# I2CRJ45X8.net
KiCad netlist of a schematic drawn in EAGLE
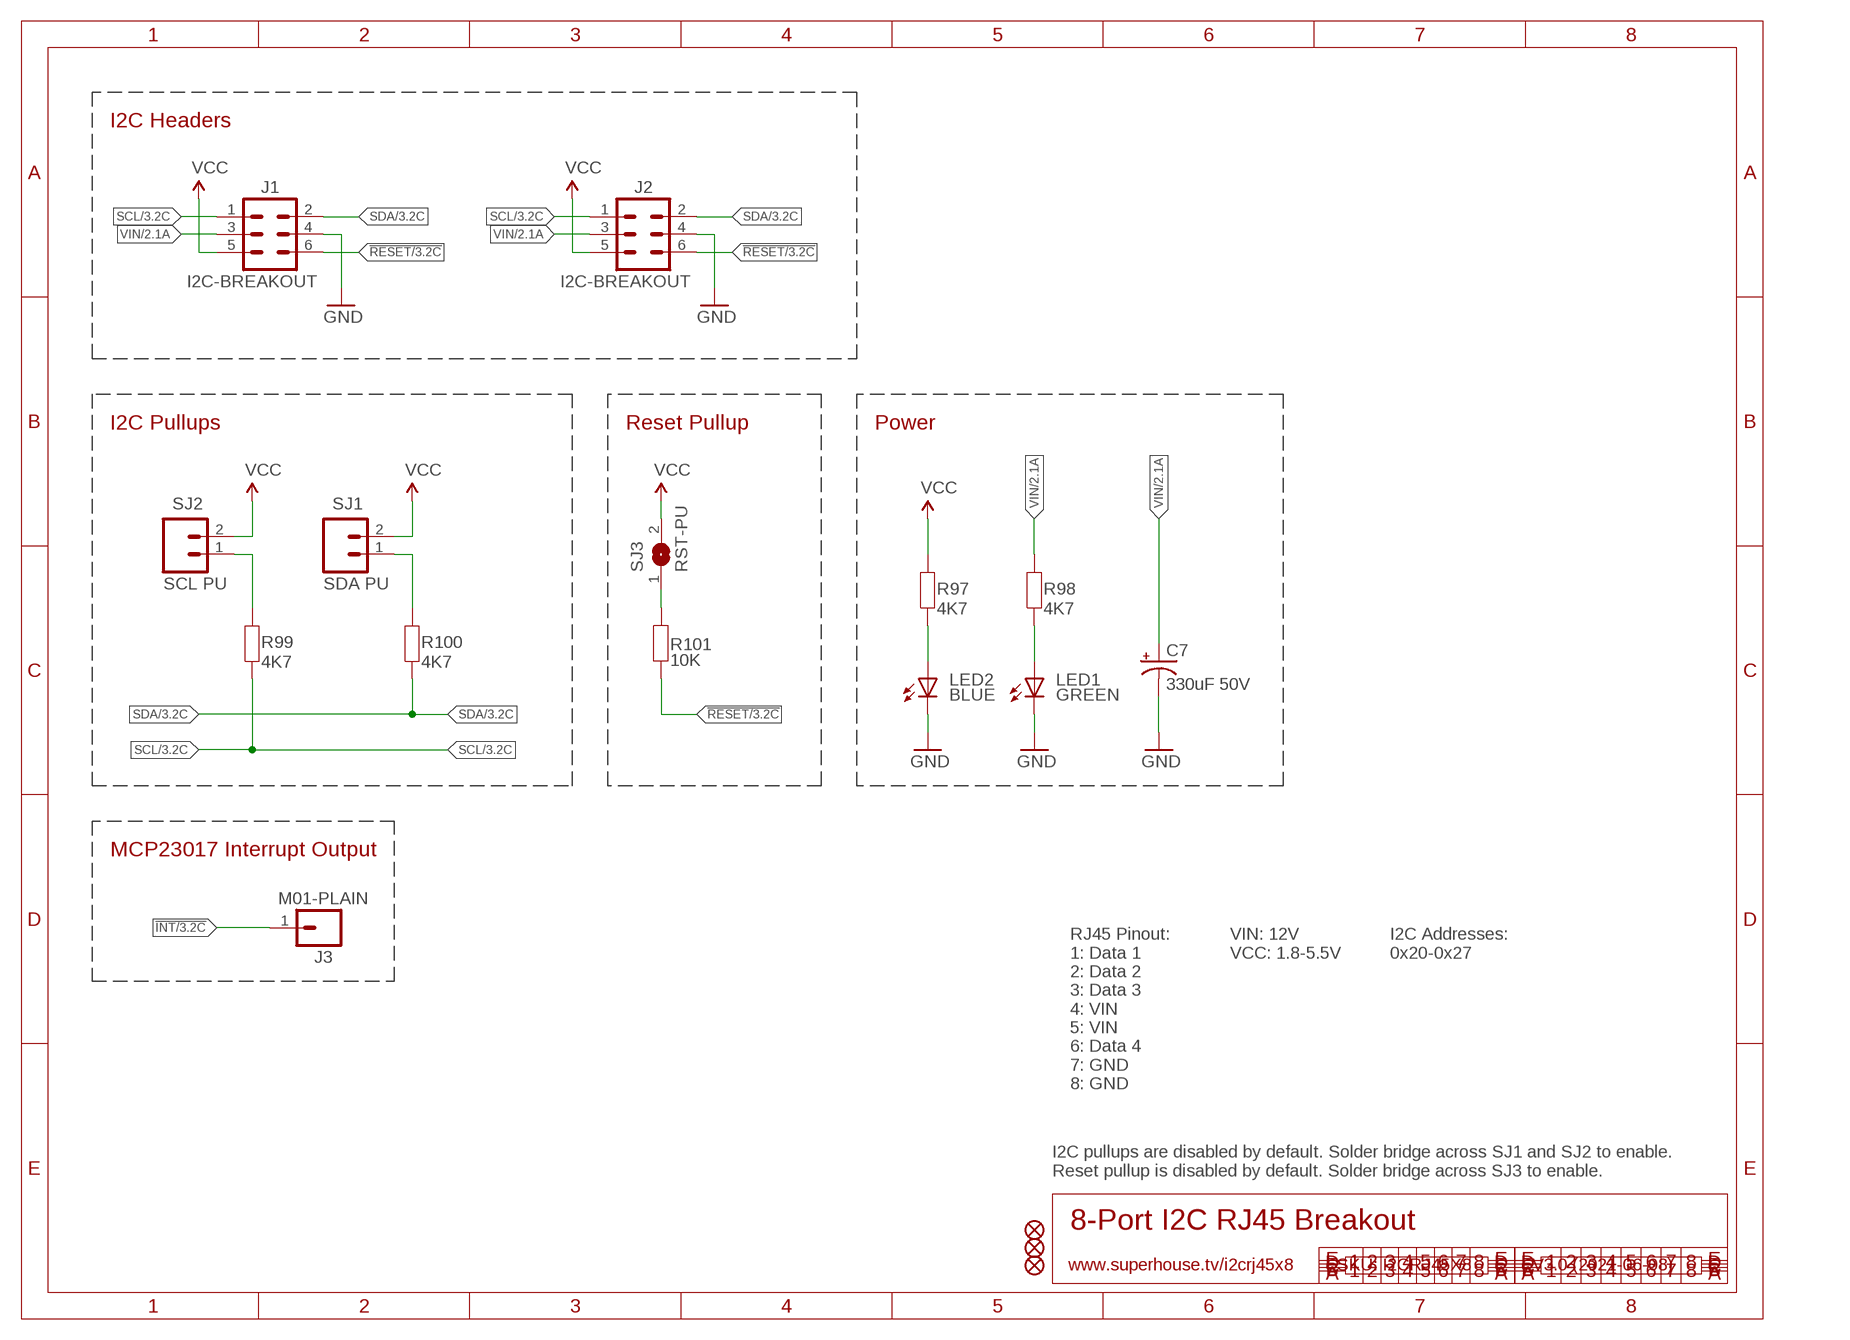
[diagram p0: schematic, sheet 1]
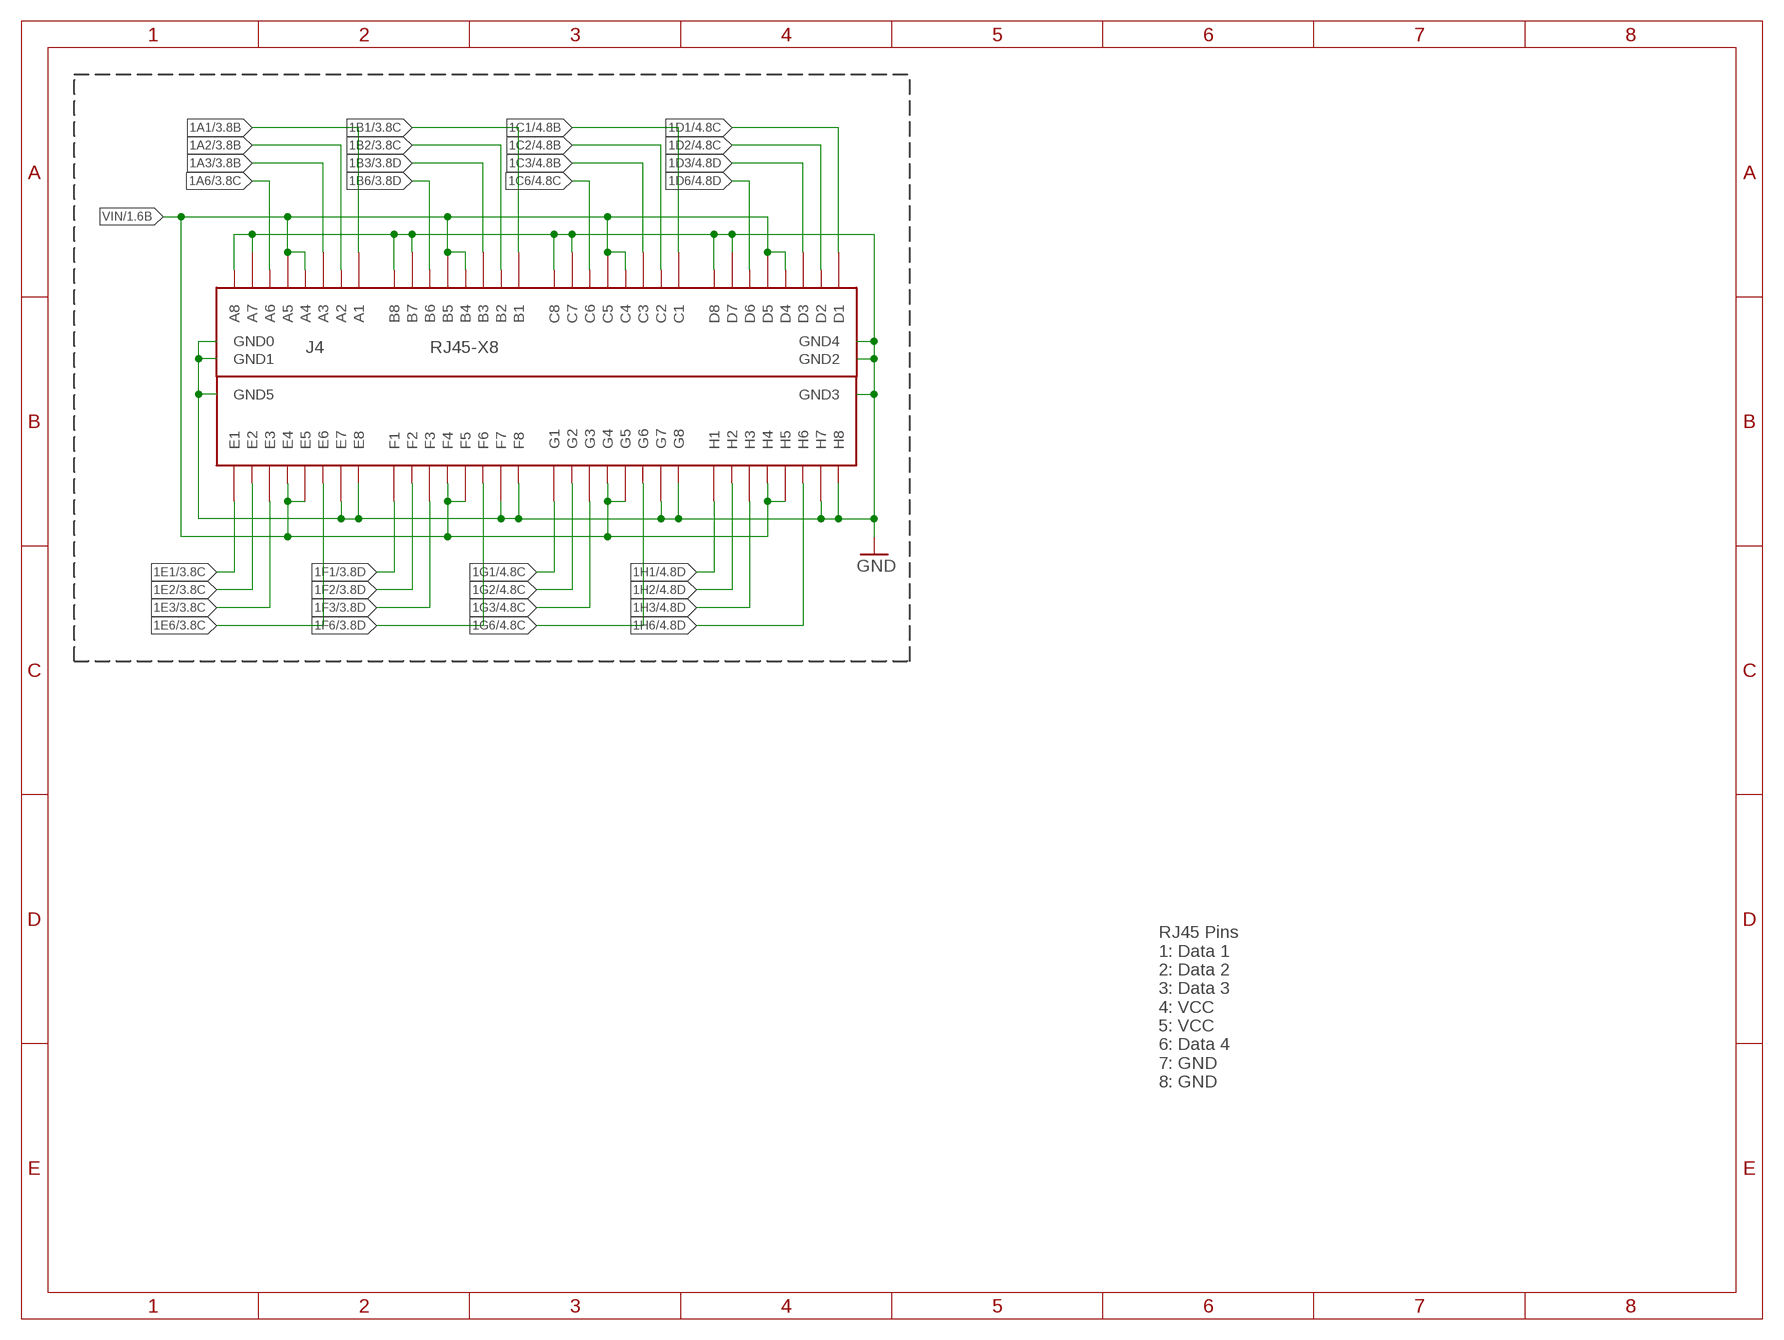
[diagram p1: schematic, sheet 2]
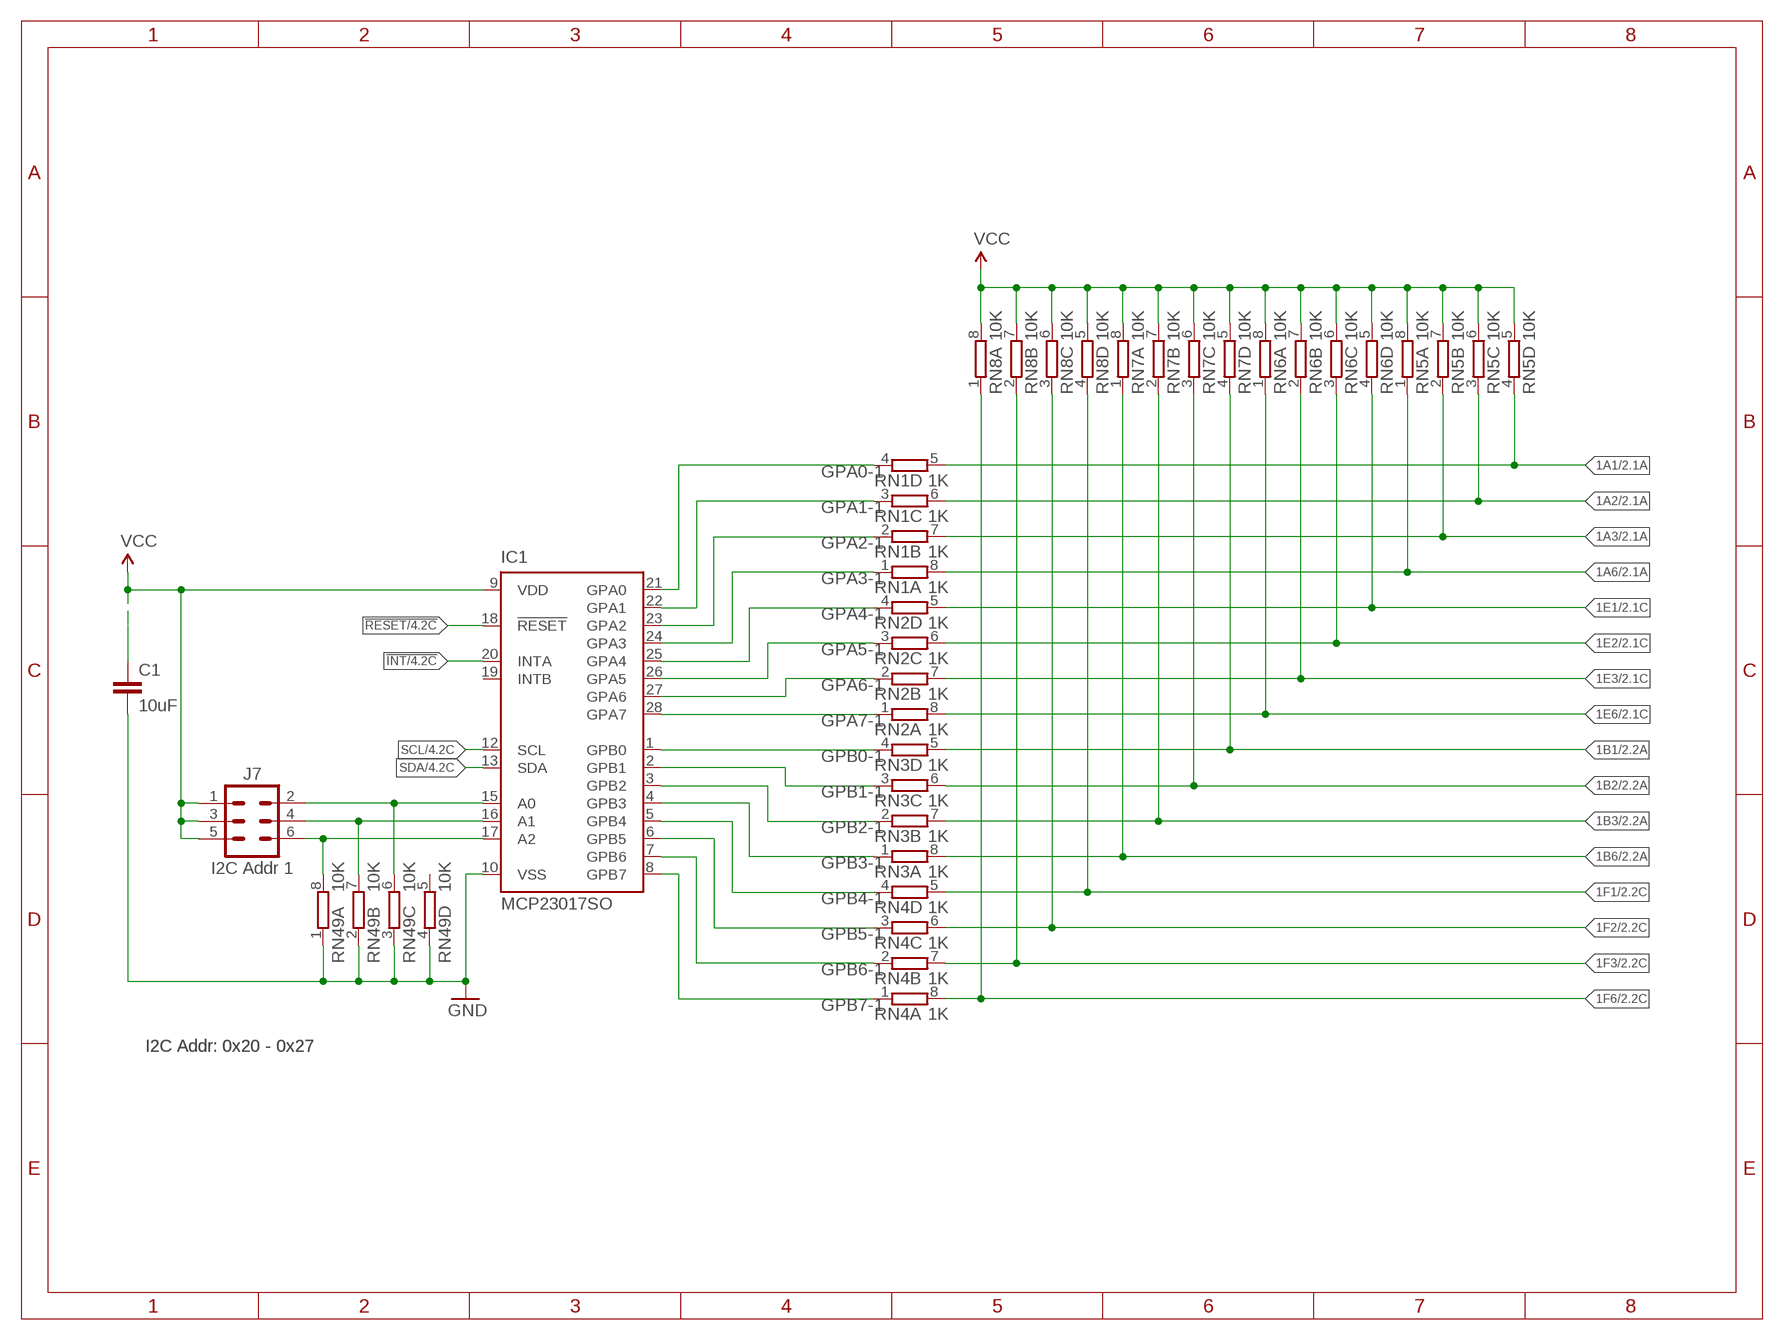
[diagram p2: schematic, sheet 3]
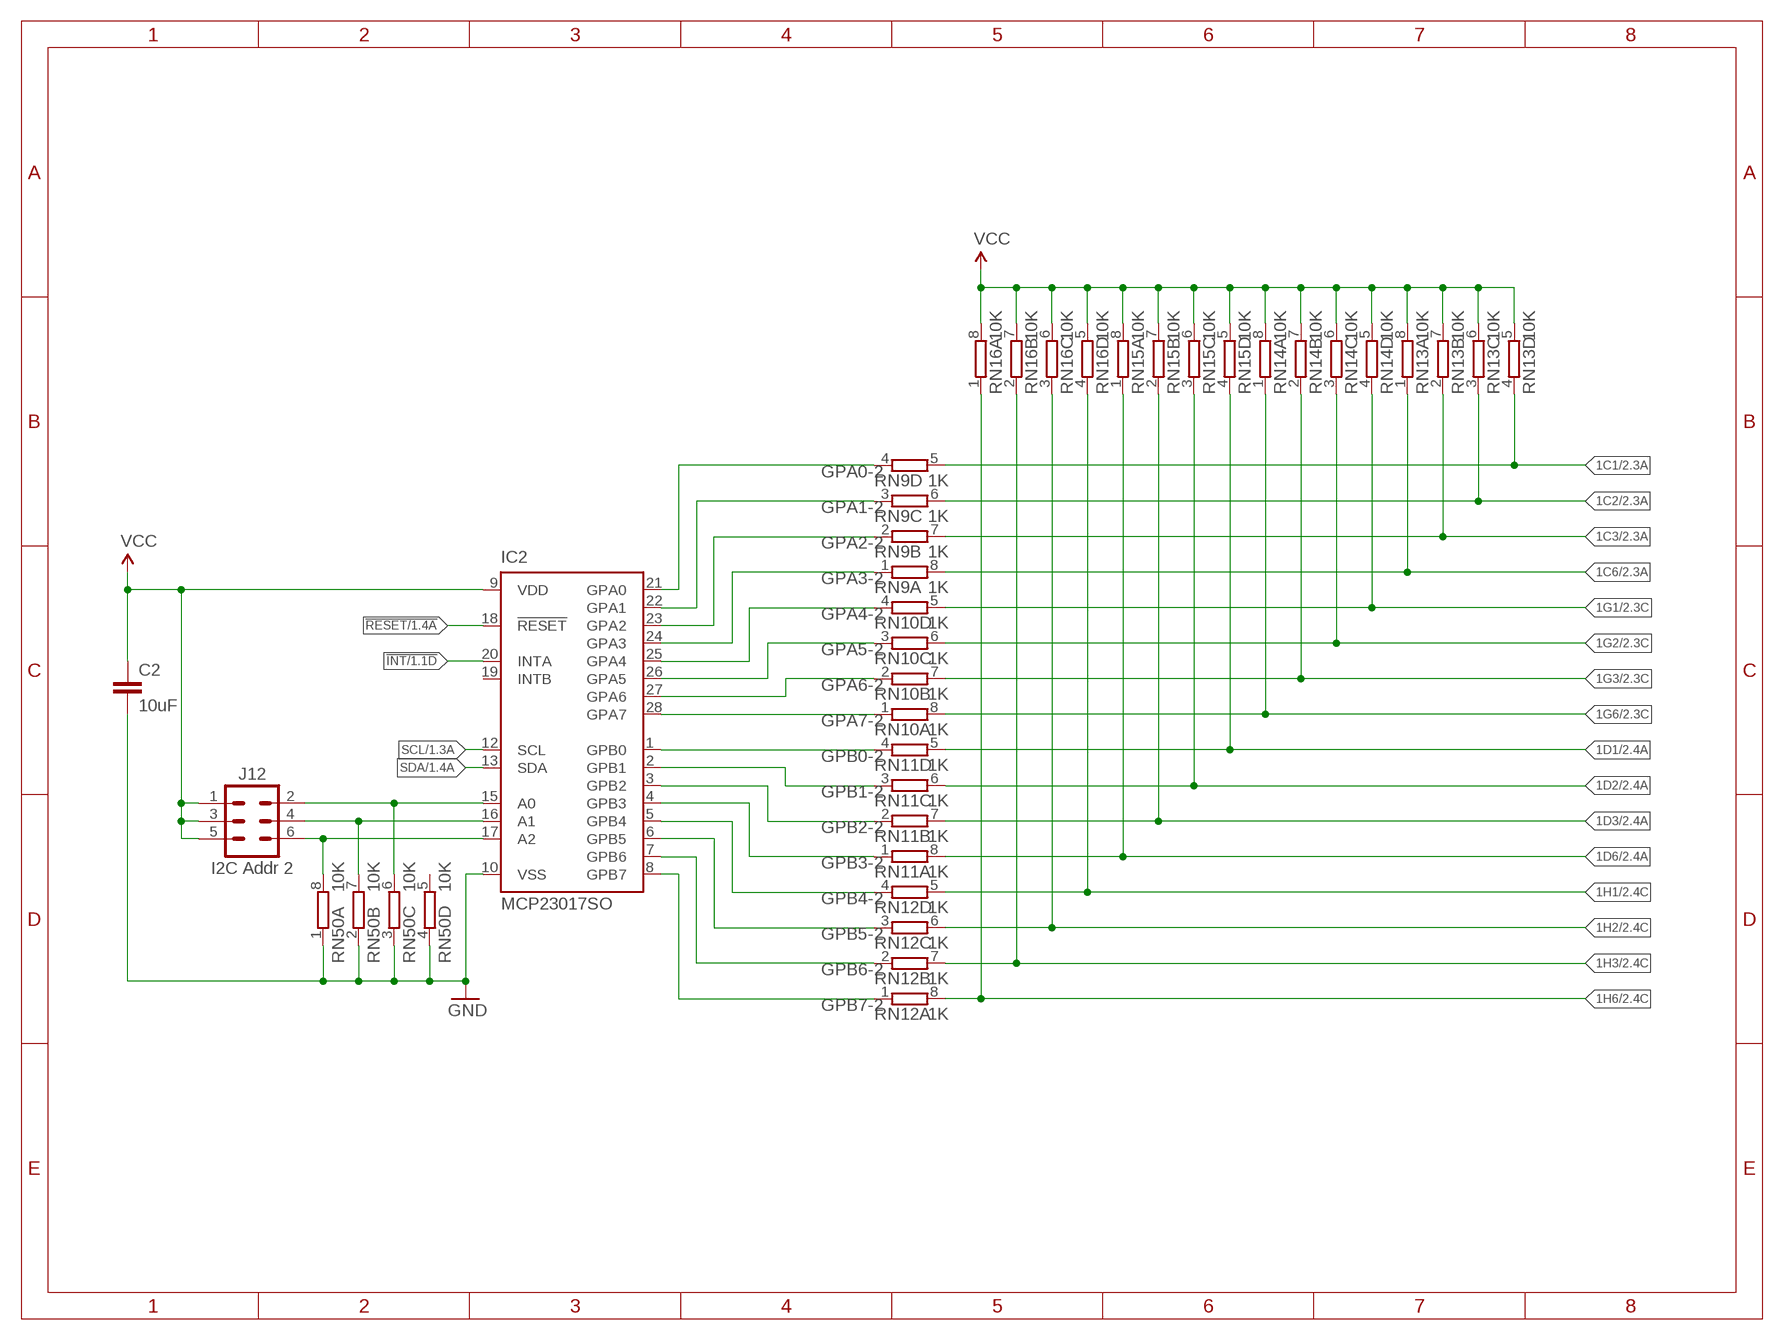
[diagram p3: schematic, sheet 4]

(export (version "E")
  (design (tool "Eeschema 10.0.6"))
  (components
    (comp (ref "C2")
      (value "10uF")
      (footprint "eagle-import:C0805")
      (libsource (lib "eagle-import") (part "CAP0805"))
    )
    (comp (ref "IC2")
      (value "MCP23017SO")
      (footprint "eagle-import:SO28W")
      (libsource (lib "eagle-import") (part "MCP23017SO"))
    )
    (comp (ref "J12")
      (value "I2C Addr 2")
      (footprint "eagle-import:2X03-P")
      (libsource (lib "eagle-import") (part "M02X3-PIN"))
    )
    (comp (ref "RN9")
      (value "1K")
      (footprint "eagle-import:CAY16")
      (libsource (lib "eagle-import") (part "4R-NCAY16"))
    )
    (comp (ref "RN10")
      (value "1K")
      (footprint "eagle-import:CAY16")
      (libsource (lib "eagle-import") (part "4R-NCAY16"))
    )
    (comp (ref "RN11")
      (value "1K")
      (footprint "eagle-import:CAY16")
      (libsource (lib "eagle-import") (part "4R-NCAY16"))
    )
    (comp (ref "RN12")
      (value "1K")
      (footprint "eagle-import:CAY16")
      (libsource (lib "eagle-import") (part "4R-NCAY16"))
    )
    (comp (ref "RN13")
      (value "10K")
      (footprint "eagle-import:CAY16")
      (libsource (lib "eagle-import") (part "4R-NCAY16"))
    )
    (comp (ref "RN14")
      (value "10K")
      (footprint "eagle-import:CAY16")
      (libsource (lib "eagle-import") (part "4R-NCAY16"))
    )
    (comp (ref "RN15")
      (value "10K")
      (footprint "eagle-import:CAY16")
      (libsource (lib "eagle-import") (part "4R-NCAY16"))
    )
    (comp (ref "RN16")
      (value "10K")
      (footprint "eagle-import:CAY16")
      (libsource (lib "eagle-import") (part "4R-NCAY16"))
    )
    (comp (ref "RN50")
      (value "10K")
      (footprint "eagle-import:CAY16")
      (libsource (lib "eagle-import") (part "4R-NCAY16"))
    )
    (comp (ref "J4")
      (value "RJ45-X8")
      (footprint "eagle-import:RJ45-2X4")
      (libsource (lib "eagle-import") (part "RJ45-X8"))
    )
    (comp (ref "C7")
      (value "330uF 50V")
      (footprint "eagle-import:PANASONIC_G")
      (libsource (lib "eagle-import") (part "CAP_POLG"))
    )
    (comp (ref "FID1")
      (value "FIDUCIAL1X2.5")
      (footprint "eagle-import:FIDUCIAL-1X2.5")
      (libsource (lib "eagle-import") (part "FIDUCIAL1X2.5"))
    )
    (comp (ref "FID2")
      (value "FIDUCIAL1X2.5")
      (footprint "eagle-import:FIDUCIAL-1X2.5")
      (libsource (lib "eagle-import") (part "FIDUCIAL1X2.5"))
    )
    (comp (ref "FID3")
      (value "FIDUCIAL1X2.5")
      (footprint "eagle-import:FIDUCIAL-1X2.5")
      (libsource (lib "eagle-import") (part "FIDUCIAL1X2.5"))
    )
    (comp (ref "J1")
      (value "I2C-BREAKOUT")
      (footprint "eagle-import:2X3-2.54-SHROUDED")
      (libsource (lib "eagle-import") (part "M02X3-SHROUDED"))
    )
    (comp (ref "J2")
      (value "I2C-BREAKOUT")
      (footprint "eagle-import:2X3-2.54-SHROUDED")
      (libsource (lib "eagle-import") (part "M02X3-SHROUDED"))
    )
    (comp (ref "J3")
      (value "M01-PLAIN")
      (footprint "eagle-import:1X01")
      (libsource (lib "eagle-import") (part "M01-PLAIN"))
    )
    (comp (ref "LED1")
      (value "GREEN")
      (footprint "eagle-import:LED-0603")
      (libsource (lib "eagle-import") (part "LED0603"))
    )
    (comp (ref "LED2")
      (value "BLUE")
      (footprint "eagle-import:LED-0603")
      (libsource (lib "eagle-import") (part "LED0603"))
    )
    (comp (ref "R97")
      (value "4K7")
      (footprint "eagle-import:R0603")
      (libsource (lib "eagle-import") (part "RESISTOR0603"))
    )
    (comp (ref "R98")
      (value "4K7")
      (footprint "eagle-import:R0603")
      (libsource (lib "eagle-import") (part "RESISTOR0603"))
    )
    (comp (ref "R99")
      (value "4K7")
      (footprint "eagle-import:R0603")
      (libsource (lib "eagle-import") (part "RESISTOR0603"))
    )
    (comp (ref "R100")
      (value "4K7")
      (footprint "eagle-import:R0603")
      (libsource (lib "eagle-import") (part "RESISTOR0603"))
    )
    (comp (ref "R101")
      (value "10K")
      (footprint "eagle-import:R0603")
      (libsource (lib "eagle-import") (part "RESISTOR0603"))
    )
    (comp (ref "SJ1")
      (value "SDA PU")
      (footprint "eagle-import:1X02-P")
      (libsource (lib "eagle-import") (part "M02-PIN"))
    )
    (comp (ref "SJ2")
      (value "SCL PU")
      (footprint "eagle-import:1X02-P")
      (libsource (lib "eagle-import") (part "M02-PIN"))
    )
    (comp (ref "SJ3")
      (value "RST-PU")
      (footprint "eagle-import:SJ")
      (libsource (lib "eagle-import") (part "SJ-NORMAL"))
    )
    (comp (ref "C1")
      (value "10uF")
      (footprint "eagle-import:C0805")
      (libsource (lib "eagle-import") (part "CAP0805"))
    )
    (comp (ref "IC1")
      (value "MCP23017SO")
      (footprint "eagle-import:SO28W")
      (libsource (lib "eagle-import") (part "MCP23017SO"))
    )
    (comp (ref "J7")
      (value "I2C Addr 1")
      (footprint "eagle-import:2X03-P")
      (libsource (lib "eagle-import") (part "M02X3-PIN"))
    )
    (comp (ref "RN1")
      (value "1K")
      (footprint "eagle-import:CAY16")
      (libsource (lib "eagle-import") (part "4R-NCAY16"))
    )
    (comp (ref "RN2")
      (value "1K")
      (footprint "eagle-import:CAY16")
      (libsource (lib "eagle-import") (part "4R-NCAY16"))
    )
    (comp (ref "RN3")
      (value "1K")
      (footprint "eagle-import:CAY16")
      (libsource (lib "eagle-import") (part "4R-NCAY16"))
    )
    (comp (ref "RN4")
      (value "1K")
      (footprint "eagle-import:CAY16")
      (libsource (lib "eagle-import") (part "4R-NCAY16"))
    )
    (comp (ref "RN5")
      (value "10K")
      (footprint "eagle-import:CAY16")
      (libsource (lib "eagle-import") (part "4R-NCAY16"))
    )
    (comp (ref "RN6")
      (value "10K")
      (footprint "eagle-import:CAY16")
      (libsource (lib "eagle-import") (part "4R-NCAY16"))
    )
    (comp (ref "RN7")
      (value "10K")
      (footprint "eagle-import:CAY16")
      (libsource (lib "eagle-import") (part "4R-NCAY16"))
    )
    (comp (ref "RN8")
      (value "10K")
      (footprint "eagle-import:CAY16")
      (libsource (lib "eagle-import") (part "4R-NCAY16"))
    )
    (comp (ref "RN49")
      (value "10K")
      (footprint "eagle-import:CAY16")
      (libsource (lib "eagle-import") (part "4R-NCAY16"))
    )
  )
  (nets
    (net (code "1") (name "1A1") (class "Default")
      (node (ref "J4") (pin "A1") (pinfunction "A1_A1") (pintype "bidirectional"))
      (node (ref "RN1") (pin "5") (pinfunction "2_5") (pintype "passive"))
      (node (ref "RN5") (pin "4") (pinfunction "1_4") (pintype "passive"))
    )
    (net (code "2") (name "1A2") (class "Default")
      (node (ref "J4") (pin "A2") (pinfunction "A2_A2") (pintype "bidirectional"))
      (node (ref "RN1") (pin "6") (pinfunction "2_6") (pintype "passive"))
      (node (ref "RN5") (pin "3") (pinfunction "1_3") (pintype "passive"))
    )
    (net (code "3") (name "1A3") (class "Default")
      (node (ref "J4") (pin "A3") (pinfunction "A3_A3") (pintype "bidirectional"))
      (node (ref "RN1") (pin "7") (pinfunction "2_7") (pintype "passive"))
      (node (ref "RN5") (pin "2") (pinfunction "1_2") (pintype "passive"))
    )
    (net (code "4") (name "1A6") (class "Default")
      (node (ref "J4") (pin "A6") (pinfunction "A6_A6") (pintype "bidirectional"))
      (node (ref "RN1") (pin "8") (pinfunction "2_8") (pintype "passive"))
      (node (ref "RN5") (pin "1") (pinfunction "1_1") (pintype "passive"))
    )
    (net (code "5") (name "1B1") (class "Default")
      (node (ref "J4") (pin "B1") (pinfunction "B1_B1") (pintype "bidirectional"))
      (node (ref "RN3") (pin "5") (pinfunction "2_5") (pintype "passive"))
      (node (ref "RN7") (pin "4") (pinfunction "1_4") (pintype "passive"))
    )
    (net (code "6") (name "1B2") (class "Default")
      (node (ref "J4") (pin "B2") (pinfunction "B2_B2") (pintype "bidirectional"))
      (node (ref "RN3") (pin "6") (pinfunction "2_6") (pintype "passive"))
      (node (ref "RN7") (pin "3") (pinfunction "1_3") (pintype "passive"))
    )
    (net (code "7") (name "1B3") (class "Default")
      (node (ref "J4") (pin "B3") (pinfunction "B3_B3") (pintype "bidirectional"))
      (node (ref "RN3") (pin "7") (pinfunction "2_7") (pintype "passive"))
      (node (ref "RN7") (pin "2") (pinfunction "1_2") (pintype "passive"))
    )
    (net (code "8") (name "1B6") (class "Default")
      (node (ref "J4") (pin "B6") (pinfunction "B6_B6") (pintype "bidirectional"))
      (node (ref "RN3") (pin "8") (pinfunction "2_8") (pintype "passive"))
      (node (ref "RN7") (pin "1") (pinfunction "1_1") (pintype "passive"))
    )
    (net (code "9") (name "1C1") (class "Default")
      (node (ref "J4") (pin "C1") (pinfunction "C1_C1") (pintype "bidirectional"))
      (node (ref "RN13") (pin "4") (pinfunction "1_4") (pintype "passive"))
      (node (ref "RN9") (pin "5") (pinfunction "2_5") (pintype "passive"))
    )
    (net (code "10") (name "1C2") (class "Default")
      (node (ref "J4") (pin "C2") (pinfunction "C2_C2") (pintype "bidirectional"))
      (node (ref "RN13") (pin "3") (pinfunction "1_3") (pintype "passive"))
      (node (ref "RN9") (pin "6") (pinfunction "2_6") (pintype "passive"))
    )
    (net (code "11") (name "1C3") (class "Default")
      (node (ref "J4") (pin "C3") (pinfunction "C3_C3") (pintype "bidirectional"))
      (node (ref "RN13") (pin "2") (pinfunction "1_2") (pintype "passive"))
      (node (ref "RN9") (pin "7") (pinfunction "2_7") (pintype "passive"))
    )
    (net (code "12") (name "1C6") (class "Default")
      (node (ref "J4") (pin "C6") (pinfunction "C6_C6") (pintype "bidirectional"))
      (node (ref "RN13") (pin "1") (pinfunction "1_1") (pintype "passive"))
      (node (ref "RN9") (pin "8") (pinfunction "2_8") (pintype "passive"))
    )
    (net (code "13") (name "1D1") (class "Default")
      (node (ref "J4") (pin "D1") (pinfunction "D1_D1") (pintype "bidirectional"))
      (node (ref "RN11") (pin "5") (pinfunction "2_5") (pintype "passive"))
      (node (ref "RN15") (pin "4") (pinfunction "1_4") (pintype "passive"))
    )
    (net (code "14") (name "1D2") (class "Default")
      (node (ref "J4") (pin "D2") (pinfunction "D2_D2") (pintype "bidirectional"))
      (node (ref "RN11") (pin "6") (pinfunction "2_6") (pintype "passive"))
      (node (ref "RN15") (pin "3") (pinfunction "1_3") (pintype "passive"))
    )
    (net (code "15") (name "1D3") (class "Default")
      (node (ref "J4") (pin "D3") (pinfunction "D3_D3") (pintype "bidirectional"))
      (node (ref "RN11") (pin "7") (pinfunction "2_7") (pintype "passive"))
      (node (ref "RN15") (pin "2") (pinfunction "1_2") (pintype "passive"))
    )
    (net (code "16") (name "1D6") (class "Default")
      (node (ref "J4") (pin "D6") (pinfunction "D6_D6") (pintype "bidirectional"))
      (node (ref "RN11") (pin "8") (pinfunction "2_8") (pintype "passive"))
      (node (ref "RN15") (pin "1") (pinfunction "1_1") (pintype "passive"))
    )
    (net (code "17") (name "1E1") (class "Default")
      (node (ref "J4") (pin "E1") (pinfunction "E1_E1") (pintype "bidirectional"))
      (node (ref "RN2") (pin "5") (pinfunction "2_5") (pintype "passive"))
      (node (ref "RN6") (pin "4") (pinfunction "1_4") (pintype "passive"))
    )
    (net (code "18") (name "1E2") (class "Default")
      (node (ref "J4") (pin "E2") (pinfunction "E2_E2") (pintype "bidirectional"))
      (node (ref "RN2") (pin "6") (pinfunction "2_6") (pintype "passive"))
      (node (ref "RN6") (pin "3") (pinfunction "1_3") (pintype "passive"))
    )
    (net (code "19") (name "1E3") (class "Default")
      (node (ref "J4") (pin "E3") (pinfunction "E3_E3") (pintype "bidirectional"))
      (node (ref "RN2") (pin "7") (pinfunction "2_7") (pintype "passive"))
      (node (ref "RN6") (pin "2") (pinfunction "1_2") (pintype "passive"))
    )
    (net (code "20") (name "1E6") (class "Default")
      (node (ref "J4") (pin "E6") (pinfunction "E6_E6") (pintype "bidirectional"))
      (node (ref "RN2") (pin "8") (pinfunction "2_8") (pintype "passive"))
      (node (ref "RN6") (pin "1") (pinfunction "1_1") (pintype "passive"))
    )
    (net (code "21") (name "1F1") (class "Default")
      (node (ref "J4") (pin "F1") (pinfunction "F1_F1") (pintype "bidirectional"))
      (node (ref "RN4") (pin "5") (pinfunction "2_5") (pintype "passive"))
      (node (ref "RN8") (pin "4") (pinfunction "1_4") (pintype "passive"))
    )
    (net (code "22") (name "1F2") (class "Default")
      (node (ref "J4") (pin "F2") (pinfunction "F2_F2") (pintype "bidirectional"))
      (node (ref "RN4") (pin "6") (pinfunction "2_6") (pintype "passive"))
      (node (ref "RN8") (pin "3") (pinfunction "1_3") (pintype "passive"))
    )
    (net (code "23") (name "1F3") (class "Default")
      (node (ref "J4") (pin "F3") (pinfunction "F3_F3") (pintype "bidirectional"))
      (node (ref "RN4") (pin "7") (pinfunction "2_7") (pintype "passive"))
      (node (ref "RN8") (pin "2") (pinfunction "1_2") (pintype "passive"))
    )
    (net (code "24") (name "1F6") (class "Default")
      (node (ref "J4") (pin "F6") (pinfunction "F6_F6") (pintype "bidirectional"))
      (node (ref "RN4") (pin "8") (pinfunction "2_8") (pintype "passive"))
      (node (ref "RN8") (pin "1") (pinfunction "1_1") (pintype "passive"))
    )
    (net (code "25") (name "1G1") (class "Default")
      (node (ref "J4") (pin "G1") (pinfunction "G1_G1") (pintype "bidirectional"))
      (node (ref "RN10") (pin "5") (pinfunction "2_5") (pintype "passive"))
      (node (ref "RN14") (pin "4") (pinfunction "1_4") (pintype "passive"))
    )
    (net (code "26") (name "1G2") (class "Default")
      (node (ref "J4") (pin "G2") (pinfunction "G2_G2") (pintype "bidirectional"))
      (node (ref "RN10") (pin "6") (pinfunction "2_6") (pintype "passive"))
      (node (ref "RN14") (pin "3") (pinfunction "1_3") (pintype "passive"))
    )
    (net (code "27") (name "1G3") (class "Default")
      (node (ref "J4") (pin "G3") (pinfunction "G3_G3") (pintype "bidirectional"))
      (node (ref "RN10") (pin "7") (pinfunction "2_7") (pintype "passive"))
      (node (ref "RN14") (pin "2") (pinfunction "1_2") (pintype "passive"))
    )
    (net (code "28") (name "1G6") (class "Default")
      (node (ref "J4") (pin "G6") (pinfunction "G6_G6") (pintype "bidirectional"))
      (node (ref "RN10") (pin "8") (pinfunction "2_8") (pintype "passive"))
      (node (ref "RN14") (pin "1") (pinfunction "1_1") (pintype "passive"))
    )
    (net (code "29") (name "1H1") (class "Default")
      (node (ref "J4") (pin "H1") (pinfunction "H1_H1") (pintype "bidirectional"))
      (node (ref "RN12") (pin "5") (pinfunction "2_5") (pintype "passive"))
      (node (ref "RN16") (pin "4") (pinfunction "1_4") (pintype "passive"))
    )
    (net (code "30") (name "1H2") (class "Default")
      (node (ref "J4") (pin "H2") (pinfunction "H2_H2") (pintype "bidirectional"))
      (node (ref "RN12") (pin "6") (pinfunction "2_6") (pintype "passive"))
      (node (ref "RN16") (pin "3") (pinfunction "1_3") (pintype "passive"))
    )
    (net (code "31") (name "1H3") (class "Default")
      (node (ref "J4") (pin "H3") (pinfunction "H3_H3") (pintype "bidirectional"))
      (node (ref "RN12") (pin "7") (pinfunction "2_7") (pintype "passive"))
      (node (ref "RN16") (pin "2") (pinfunction "1_2") (pintype "passive"))
    )
    (net (code "32") (name "1H6") (class "Default")
      (node (ref "J4") (pin "H6") (pinfunction "H6_H6") (pintype "bidirectional"))
      (node (ref "RN12") (pin "8") (pinfunction "2_8") (pintype "passive"))
      (node (ref "RN16") (pin "1") (pinfunction "1_1") (pintype "passive"))
    )
    (net (code "33") (name "GND") (class "Default")
      (node (ref "C1") (pin "2") (pinfunction "2_2") (pintype "passive"))
      (node (ref "C2") (pin "2") (pinfunction "2_2") (pintype "passive"))
      (node (ref "C7") (pin "-") (pinfunction "-_-") (pintype "passive"))
      (node (ref "IC1") (pin "10") (pinfunction "VSS_10") (pintype "power_in"))
      (node (ref "IC2") (pin "10") (pinfunction "VSS_10") (pintype "power_in"))
      (node (ref "J1") (pin "4") (pinfunction "4_4") (pintype "passive"))
      (node (ref "J2") (pin "4") (pinfunction "4_4") (pintype "passive"))
      (node (ref "J4") (pin "A7") (pinfunction "A7_A7") (pintype "bidirectional"))
      (node (ref "J4") (pin "A8") (pinfunction "A8_A8") (pintype "bidirectional"))
      (node (ref "J4") (pin "B7") (pinfunction "B7_B7") (pintype "bidirectional"))
      (node (ref "J4") (pin "B8") (pinfunction "B8_B8") (pintype "bidirectional"))
      (node (ref "J4") (pin "C7") (pinfunction "C7_C7") (pintype "bidirectional"))
      (node (ref "J4") (pin "C8") (pinfunction "C8_C8") (pintype "bidirectional"))
      (node (ref "J4") (pin "D7") (pinfunction "D7_D7") (pintype "bidirectional"))
      (node (ref "J4") (pin "D8") (pinfunction "D8_D8") (pintype "bidirectional"))
      (node (ref "J4") (pin "E7") (pinfunction "E7_E7") (pintype "bidirectional"))
      (node (ref "J4") (pin "E8") (pinfunction "E8_E8") (pintype "bidirectional"))
      (node (ref "J4") (pin "F7") (pinfunction "F7_F7") (pintype "bidirectional"))
      (node (ref "J4") (pin "F8") (pinfunction "F8_F8") (pintype "bidirectional"))
      (node (ref "J4") (pin "G7") (pinfunction "G7_G7") (pintype "bidirectional"))
      (node (ref "J4") (pin "G8") (pinfunction "G8_G8") (pintype "bidirectional"))
      (node (ref "J4") (pin "GND0") (pinfunction "GND0_GND0") (pintype "power_in"))
      (node (ref "J4") (pin "GND1") (pinfunction "GND1_GND1") (pintype "power_in"))
      (node (ref "J4") (pin "GND2") (pinfunction "GND2_GND2") (pintype "power_in"))
      (node (ref "J4") (pin "GND3") (pinfunction "GND3_GND3") (pintype "power_in"))
      (node (ref "J4") (pin "GND4") (pinfunction "GND4_GND4") (pintype "power_in"))
      (node (ref "J4") (pin "GND5") (pinfunction "GND5_GND5") (pintype "power_in"))
      (node (ref "J4") (pin "H7") (pinfunction "H7_H7") (pintype "bidirectional"))
      (node (ref "J4") (pin "H8") (pinfunction "H8_H8") (pintype "bidirectional"))
      (node (ref "LED1") (pin "C") (pinfunction "C_C") (pintype "passive"))
      (node (ref "LED2") (pin "C") (pinfunction "C_C") (pintype "passive"))
      (node (ref "RN49") (pin "1") (pinfunction "1_1") (pintype "passive"))
      (node (ref "RN49") (pin "2") (pinfunction "1_2") (pintype "passive"))
      (node (ref "RN49") (pin "3") (pinfunction "1_3") (pintype "passive"))
      (node (ref "RN49") (pin "4") (pinfunction "1_4") (pintype "passive"))
      (node (ref "RN50") (pin "1") (pinfunction "1_1") (pintype "passive"))
      (node (ref "RN50") (pin "2") (pinfunction "1_2") (pintype "passive"))
      (node (ref "RN50") (pin "3") (pinfunction "1_3") (pintype "passive"))
      (node (ref "RN50") (pin "4") (pinfunction "1_4") (pintype "passive"))
    )
    (net (code "34") (name "GPA0-1") (class "Default")
      (node (ref "IC1") (pin "21") (pinfunction "GPA0_21") (pintype "bidirectional"))
      (node (ref "RN1") (pin "4") (pinfunction "1_4") (pintype "passive"))
    )
    (net (code "35") (name "GPA0-2") (class "Default")
      (node (ref "IC2") (pin "21") (pinfunction "GPA0_21") (pintype "bidirectional"))
      (node (ref "RN9") (pin "4") (pinfunction "1_4") (pintype "passive"))
    )
    (net (code "36") (name "GPA1-1") (class "Default")
      (node (ref "IC1") (pin "22") (pinfunction "GPA1_22") (pintype "bidirectional"))
      (node (ref "RN1") (pin "3") (pinfunction "1_3") (pintype "passive"))
    )
    (net (code "37") (name "GPA1-2") (class "Default")
      (node (ref "IC2") (pin "22") (pinfunction "GPA1_22") (pintype "bidirectional"))
      (node (ref "RN9") (pin "3") (pinfunction "1_3") (pintype "passive"))
    )
    (net (code "38") (name "GPA2-1") (class "Default")
      (node (ref "IC1") (pin "23") (pinfunction "GPA2_23") (pintype "bidirectional"))
      (node (ref "RN1") (pin "2") (pinfunction "1_2") (pintype "passive"))
    )
    (net (code "39") (name "GPA2-2") (class "Default")
      (node (ref "IC2") (pin "23") (pinfunction "GPA2_23") (pintype "bidirectional"))
      (node (ref "RN9") (pin "2") (pinfunction "1_2") (pintype "passive"))
    )
    (net (code "40") (name "GPA3-1") (class "Default")
      (node (ref "IC1") (pin "24") (pinfunction "GPA3_24") (pintype "bidirectional"))
      (node (ref "RN1") (pin "1") (pinfunction "1_1") (pintype "passive"))
    )
    (net (code "41") (name "GPA3-2") (class "Default")
      (node (ref "IC2") (pin "24") (pinfunction "GPA3_24") (pintype "bidirectional"))
      (node (ref "RN9") (pin "1") (pinfunction "1_1") (pintype "passive"))
    )
    (net (code "42") (name "GPA4-1") (class "Default")
      (node (ref "IC1") (pin "25") (pinfunction "GPA4_25") (pintype "bidirectional"))
      (node (ref "RN2") (pin "4") (pinfunction "1_4") (pintype "passive"))
    )
    (net (code "43") (name "GPA4-2") (class "Default")
      (node (ref "IC2") (pin "25") (pinfunction "GPA4_25") (pintype "bidirectional"))
      (node (ref "RN10") (pin "4") (pinfunction "1_4") (pintype "passive"))
    )
    (net (code "44") (name "GPA5-1") (class "Default")
      (node (ref "IC1") (pin "26") (pinfunction "GPA5_26") (pintype "bidirectional"))
      (node (ref "RN2") (pin "3") (pinfunction "1_3") (pintype "passive"))
    )
    (net (code "45") (name "GPA5-2") (class "Default")
      (node (ref "IC2") (pin "26") (pinfunction "GPA5_26") (pintype "bidirectional"))
      (node (ref "RN10") (pin "3") (pinfunction "1_3") (pintype "passive"))
    )
    (net (code "46") (name "GPA6-1") (class "Default")
      (node (ref "IC1") (pin "27") (pinfunction "GPA6_27") (pintype "bidirectional"))
      (node (ref "RN2") (pin "2") (pinfunction "1_2") (pintype "passive"))
    )
    (net (code "47") (name "GPA6-2") (class "Default")
      (node (ref "IC2") (pin "27") (pinfunction "GPA6_27") (pintype "bidirectional"))
      (node (ref "RN10") (pin "2") (pinfunction "1_2") (pintype "passive"))
    )
    (net (code "48") (name "GPA7-1") (class "Default")
      (node (ref "IC1") (pin "28") (pinfunction "GPA7_28") (pintype "bidirectional"))
      (node (ref "RN2") (pin "1") (pinfunction "1_1") (pintype "passive"))
    )
    (net (code "49") (name "GPA7-2") (class "Default")
      (node (ref "IC2") (pin "28") (pinfunction "GPA7_28") (pintype "bidirectional"))
      (node (ref "RN10") (pin "1") (pinfunction "1_1") (pintype "passive"))
    )
    (net (code "50") (name "GPB0-1") (class "Default")
      (node (ref "IC1") (pin "1") (pinfunction "GPB0_1") (pintype "bidirectional"))
      (node (ref "RN3") (pin "4") (pinfunction "1_4") (pintype "passive"))
    )
    (net (code "51") (name "GPB0-2") (class "Default")
      (node (ref "IC2") (pin "1") (pinfunction "GPB0_1") (pintype "bidirectional"))
      (node (ref "RN11") (pin "4") (pinfunction "1_4") (pintype "passive"))
    )
    (net (code "52") (name "GPB1-1") (class "Default")
      (node (ref "IC1") (pin "2") (pinfunction "GPB1_2") (pintype "bidirectional"))
      (node (ref "RN3") (pin "3") (pinfunction "1_3") (pintype "passive"))
    )
    (net (code "53") (name "GPB1-2") (class "Default")
      (node (ref "IC2") (pin "2") (pinfunction "GPB1_2") (pintype "bidirectional"))
      (node (ref "RN11") (pin "3") (pinfunction "1_3") (pintype "passive"))
    )
    (net (code "54") (name "GPB2-1") (class "Default")
      (node (ref "IC1") (pin "3") (pinfunction "GPB2_3") (pintype "bidirectional"))
      (node (ref "RN3") (pin "2") (pinfunction "1_2") (pintype "passive"))
    )
    (net (code "55") (name "GPB2-2") (class "Default")
      (node (ref "IC2") (pin "3") (pinfunction "GPB2_3") (pintype "bidirectional"))
      (node (ref "RN11") (pin "2") (pinfunction "1_2") (pintype "passive"))
    )
    (net (code "56") (name "GPB3-1") (class "Default")
      (node (ref "IC1") (pin "4") (pinfunction "GPB3_4") (pintype "bidirectional"))
      (node (ref "RN3") (pin "1") (pinfunction "1_1") (pintype "passive"))
    )
    (net (code "57") (name "GPB3-2") (class "Default")
      (node (ref "IC2") (pin "4") (pinfunction "GPB3_4") (pintype "bidirectional"))
      (node (ref "RN11") (pin "1") (pinfunction "1_1") (pintype "passive"))
    )
    (net (code "58") (name "GPB4-1") (class "Default")
      (node (ref "IC1") (pin "5") (pinfunction "GPB4_5") (pintype "bidirectional"))
      (node (ref "RN4") (pin "4") (pinfunction "1_4") (pintype "passive"))
    )
    (net (code "59") (name "GPB4-2") (class "Default")
      (node (ref "IC2") (pin "5") (pinfunction "GPB4_5") (pintype "bidirectional"))
      (node (ref "RN12") (pin "4") (pinfunction "1_4") (pintype "passive"))
    )
    (net (code "60") (name "GPB5-1") (class "Default")
      (node (ref "IC1") (pin "6") (pinfunction "GPB5_6") (pintype "bidirectional"))
      (node (ref "RN4") (pin "3") (pinfunction "1_3") (pintype "passive"))
    )
    (net (code "61") (name "GPB5-2") (class "Default")
      (node (ref "IC2") (pin "6") (pinfunction "GPB5_6") (pintype "bidirectional"))
      (node (ref "RN12") (pin "3") (pinfunction "1_3") (pintype "passive"))
    )
    (net (code "62") (name "GPB6-1") (class "Default")
      (node (ref "IC1") (pin "7") (pinfunction "GPB6_7") (pintype "bidirectional"))
      (node (ref "RN4") (pin "2") (pinfunction "1_2") (pintype "passive"))
    )
    (net (code "63") (name "GPB6-2") (class "Default")
      (node (ref "IC2") (pin "7") (pinfunction "GPB6_7") (pintype "bidirectional"))
      (node (ref "RN12") (pin "2") (pinfunction "1_2") (pintype "passive"))
    )
    (net (code "64") (name "GPB7-1") (class "Default")
      (node (ref "IC1") (pin "8") (pinfunction "GPB7_8") (pintype "bidirectional"))
      (node (ref "RN4") (pin "1") (pinfunction "1_1") (pintype "passive"))
    )
    (net (code "65") (name "GPB7-2") (class "Default")
      (node (ref "IC2") (pin "8") (pinfunction "GPB7_8") (pintype "bidirectional"))
      (node (ref "RN12") (pin "1") (pinfunction "1_1") (pintype "passive"))
    )
    (net (code "66") (name "Net-(IC1-A0)") (class "Default")
      (node (ref "IC1") (pin "15") (pinfunction "A0_15") (pintype "input"))
      (node (ref "J7") (pin "2") (pinfunction "2_2") (pintype "passive"))
      (node (ref "RN49") (pin "6") (pinfunction "2_6") (pintype "passive"))
    )
    (net (code "67") (name "Net-(IC1-A1)") (class "Default")
      (node (ref "IC1") (pin "16") (pinfunction "A1_16") (pintype "input"))
      (node (ref "J7") (pin "4") (pinfunction "4_4") (pintype "passive"))
      (node (ref "RN49") (pin "7") (pinfunction "2_7") (pintype "passive"))
    )
    (net (code "68") (name "Net-(IC1-A2)") (class "Default")
      (node (ref "IC1") (pin "17") (pinfunction "A2_17") (pintype "input"))
      (node (ref "J7") (pin "6") (pinfunction "6_6") (pintype "passive"))
      (node (ref "RN49") (pin "8") (pinfunction "2_8") (pintype "passive"))
    )
    (net (code "69") (name "Net-(IC2-A0)") (class "Default")
      (node (ref "IC2") (pin "15") (pinfunction "A0_15") (pintype "input"))
      (node (ref "J12") (pin "2") (pinfunction "2_2") (pintype "passive"))
      (node (ref "RN50") (pin "6") (pinfunction "2_6") (pintype "passive"))
    )
    (net (code "70") (name "Net-(IC2-A1)") (class "Default")
      (node (ref "IC2") (pin "16") (pinfunction "A1_16") (pintype "input"))
      (node (ref "J12") (pin "4") (pinfunction "4_4") (pintype "passive"))
      (node (ref "RN50") (pin "7") (pinfunction "2_7") (pintype "passive"))
    )
    (net (code "71") (name "Net-(IC2-A2)") (class "Default")
      (node (ref "IC2") (pin "17") (pinfunction "A2_17") (pintype "input"))
      (node (ref "J12") (pin "6") (pinfunction "6_6") (pintype "passive"))
      (node (ref "RN50") (pin "8") (pinfunction "2_8") (pintype "passive"))
    )
    (net (code "72") (name "Net-(LED1-PadA)") (class "Default")
      (node (ref "LED1") (pin "A") (pinfunction "A_A") (pintype "passive"))
      (node (ref "R98") (pin "1") (pinfunction "1_1") (pintype "passive"))
    )
    (net (code "73") (name "Net-(LED2-PadA)") (class "Default")
      (node (ref "LED2") (pin "A") (pinfunction "A_A") (pintype "passive"))
      (node (ref "R97") (pin "1") (pinfunction "1_1") (pintype "passive"))
    )
    (net (code "74") (name "Net-(R99-Pad2)") (class "Default")
      (node (ref "R99") (pin "2") (pinfunction "2_2") (pintype "passive"))
      (node (ref "SJ2") (pin "1") (pinfunction "1_1") (pintype "passive"))
    )
    (net (code "75") (name "Net-(R100-Pad2)") (class "Default")
      (node (ref "R100") (pin "2") (pinfunction "2_2") (pintype "passive"))
      (node (ref "SJ1") (pin "1") (pinfunction "1_1") (pintype "passive"))
    )
    (net (code "76") (name "Net-(R101-Pad2)") (class "Default")
      (node (ref "R101") (pin "2") (pinfunction "2_2") (pintype "passive"))
      (node (ref "SJ3") (pin "1") (pinfunction "1_1") (pintype "passive"))
    )
    (net (code "77") (name "SCL") (class "Default")
      (node (ref "IC1") (pin "12") (pinfunction "SCL_12") (pintype "input"))
      (node (ref "IC2") (pin "12") (pinfunction "SCL_12") (pintype "input"))
      (node (ref "J1") (pin "1") (pinfunction "1_1") (pintype "passive"))
      (node (ref "J2") (pin "1") (pinfunction "1_1") (pintype "passive"))
      (node (ref "R99") (pin "1") (pinfunction "1_1") (pintype "passive"))
    )
    (net (code "78") (name "SDA") (class "Default")
      (node (ref "IC1") (pin "13") (pinfunction "SDA_13") (pintype "bidirectional"))
      (node (ref "IC2") (pin "13") (pinfunction "SDA_13") (pintype "bidirectional"))
      (node (ref "J1") (pin "2") (pinfunction "2_2") (pintype "passive"))
      (node (ref "J2") (pin "2") (pinfunction "2_2") (pintype "passive"))
      (node (ref "R100") (pin "1") (pinfunction "1_1") (pintype "passive"))
    )
    (net (code "79") (name "VCC") (class "Default")
      (node (ref "C1") (pin "1") (pinfunction "1_1") (pintype "passive"))
      (node (ref "C2") (pin "1") (pinfunction "1_1") (pintype "passive"))
      (node (ref "IC1") (pin "9") (pinfunction "VDD_9") (pintype "power_in"))
      (node (ref "IC2") (pin "9") (pinfunction "VDD_9") (pintype "power_in"))
      (node (ref "J1") (pin "5") (pinfunction "5_5") (pintype "passive"))
      (node (ref "J12") (pin "1") (pinfunction "1_1") (pintype "passive"))
      (node (ref "J12") (pin "3") (pinfunction "3_3") (pintype "passive"))
      (node (ref "J12") (pin "5") (pinfunction "5_5") (pintype "passive"))
      (node (ref "J2") (pin "5") (pinfunction "5_5") (pintype "passive"))
      (node (ref "J7") (pin "1") (pinfunction "1_1") (pintype "passive"))
      (node (ref "J7") (pin "3") (pinfunction "3_3") (pintype "passive"))
      (node (ref "J7") (pin "5") (pinfunction "5_5") (pintype "passive"))
      (node (ref "R97") (pin "2") (pinfunction "2_2") (pintype "passive"))
      (node (ref "RN13") (pin "5") (pinfunction "2_5") (pintype "passive"))
      (node (ref "RN13") (pin "6") (pinfunction "2_6") (pintype "passive"))
      (node (ref "RN13") (pin "7") (pinfunction "2_7") (pintype "passive"))
      (node (ref "RN13") (pin "8") (pinfunction "2_8") (pintype "passive"))
      (node (ref "RN14") (pin "5") (pinfunction "2_5") (pintype "passive"))
      (node (ref "RN14") (pin "6") (pinfunction "2_6") (pintype "passive"))
      (node (ref "RN14") (pin "7") (pinfunction "2_7") (pintype "passive"))
      (node (ref "RN14") (pin "8") (pinfunction "2_8") (pintype "passive"))
      (node (ref "RN15") (pin "5") (pinfunction "2_5") (pintype "passive"))
      (node (ref "RN15") (pin "6") (pinfunction "2_6") (pintype "passive"))
      (node (ref "RN15") (pin "7") (pinfunction "2_7") (pintype "passive"))
      (node (ref "RN15") (pin "8") (pinfunction "2_8") (pintype "passive"))
      (node (ref "RN16") (pin "5") (pinfunction "2_5") (pintype "passive"))
      (node (ref "RN16") (pin "6") (pinfunction "2_6") (pintype "passive"))
      (node (ref "RN16") (pin "7") (pinfunction "2_7") (pintype "passive"))
      (node (ref "RN16") (pin "8") (pinfunction "2_8") (pintype "passive"))
      (node (ref "RN5") (pin "5") (pinfunction "2_5") (pintype "passive"))
      (node (ref "RN5") (pin "6") (pinfunction "2_6") (pintype "passive"))
      (node (ref "RN5") (pin "7") (pinfunction "2_7") (pintype "passive"))
      (node (ref "RN5") (pin "8") (pinfunction "2_8") (pintype "passive"))
      (node (ref "RN6") (pin "5") (pinfunction "2_5") (pintype "passive"))
      (node (ref "RN6") (pin "6") (pinfunction "2_6") (pintype "passive"))
      (node (ref "RN6") (pin "7") (pinfunction "2_7") (pintype "passive"))
      (node (ref "RN6") (pin "8") (pinfunction "2_8") (pintype "passive"))
      (node (ref "RN7") (pin "5") (pinfunction "2_5") (pintype "passive"))
      (node (ref "RN7") (pin "6") (pinfunction "2_6") (pintype "passive"))
      (node (ref "RN7") (pin "7") (pinfunction "2_7") (pintype "passive"))
      (node (ref "RN7") (pin "8") (pinfunction "2_8") (pintype "passive"))
      (node (ref "RN8") (pin "5") (pinfunction "2_5") (pintype "passive"))
      (node (ref "RN8") (pin "6") (pinfunction "2_6") (pintype "passive"))
      (node (ref "RN8") (pin "7") (pinfunction "2_7") (pintype "passive"))
      (node (ref "RN8") (pin "8") (pinfunction "2_8") (pintype "passive"))
      (node (ref "SJ1") (pin "2") (pinfunction "2_2") (pintype "passive"))
      (node (ref "SJ2") (pin "2") (pinfunction "2_2") (pintype "passive"))
      (node (ref "SJ3") (pin "2") (pinfunction "2_2") (pintype "passive"))
    )
    (net (code "80") (name "VIN") (class "Default")
      (node (ref "C7") (pin "+") (pinfunction "+_+") (pintype "passive"))
      (node (ref "J1") (pin "3") (pinfunction "3_3") (pintype "passive"))
      (node (ref "J2") (pin "3") (pinfunction "3_3") (pintype "passive"))
      (node (ref "J4") (pin "A4") (pinfunction "A4_A4") (pintype "bidirectional"))
      (node (ref "J4") (pin "A5") (pinfunction "A5_A5") (pintype "bidirectional"))
      (node (ref "J4") (pin "B4") (pinfunction "B4_B4") (pintype "bidirectional"))
      (node (ref "J4") (pin "B5") (pinfunction "B5_B5") (pintype "bidirectional"))
      (node (ref "J4") (pin "C4") (pinfunction "C4_C4") (pintype "bidirectional"))
      (node (ref "J4") (pin "C5") (pinfunction "C5_C5") (pintype "bidirectional"))
      (node (ref "J4") (pin "D4") (pinfunction "D4_D4") (pintype "bidirectional"))
      (node (ref "J4") (pin "D5") (pinfunction "D5_D5") (pintype "bidirectional"))
      (node (ref "J4") (pin "E4") (pinfunction "E4_E4") (pintype "bidirectional"))
      (node (ref "J4") (pin "E5") (pinfunction "E5_E5") (pintype "bidirectional"))
      (node (ref "J4") (pin "F4") (pinfunction "F4_F4") (pintype "bidirectional"))
      (node (ref "J4") (pin "F5") (pinfunction "F5_F5") (pintype "bidirectional"))
      (node (ref "J4") (pin "G4") (pinfunction "G4_G4") (pintype "bidirectional"))
      (node (ref "J4") (pin "G5") (pinfunction "G5_G5") (pintype "bidirectional"))
      (node (ref "J4") (pin "H4") (pinfunction "H4_H4") (pintype "bidirectional"))
      (node (ref "J4") (pin "H5") (pinfunction "H5_H5") (pintype "bidirectional"))
      (node (ref "R98") (pin "2") (pinfunction "2_2") (pintype "passive"))
    )
    (net (code "81") (name "unconnected-(IC1-INTB-Pad19)") (class "Default")
      (node (ref "IC1") (pin "19") (pinfunction "INTB_19") (pintype "output"))
    )
    (net (code "82") (name "unconnected-(IC2-INTB-Pad19)") (class "Default")
      (node (ref "IC2") (pin "19") (pinfunction "INTB_19") (pintype "output"))
    )
    (net (code "83") (name "unconnected-(RN49D-2-Pad5)") (class "Default")
      (node (ref "RN49") (pin "5") (pinfunction "2_5") (pintype "passive"))
    )
    (net (code "84") (name "unconnected-(RN50D-2-Pad5)") (class "Default")
      (node (ref "RN50") (pin "5") (pinfunction "2_5") (pintype "passive"))
    )
    (net (code "85") (name "~{INT}") (class "Default")
      (node (ref "IC1") (pin "20") (pinfunction "INTA_20") (pintype "output"))
      (node (ref "IC2") (pin "20") (pinfunction "INTA_20") (pintype "output"))
      (node (ref "J3") (pin "1") (pinfunction "1_1") (pintype "passive"))
    )
    (net (code "86") (name "~{RESET}") (class "Default")
      (node (ref "IC1") (pin "18") (pinfunction "~{RESET}_18") (pintype "input"))
      (node (ref "IC2") (pin "18") (pinfunction "~{RESET}_18") (pintype "input"))
      (node (ref "J1") (pin "6") (pinfunction "6_6") (pintype "passive"))
      (node (ref "J2") (pin "6") (pinfunction "6_6") (pintype "passive"))
      (node (ref "R101") (pin "1") (pinfunction "1_1") (pintype "passive"))
    )
  )
)
